# type-1_4_button.net
KiCad netlist of a schematic drawn in EAGLE
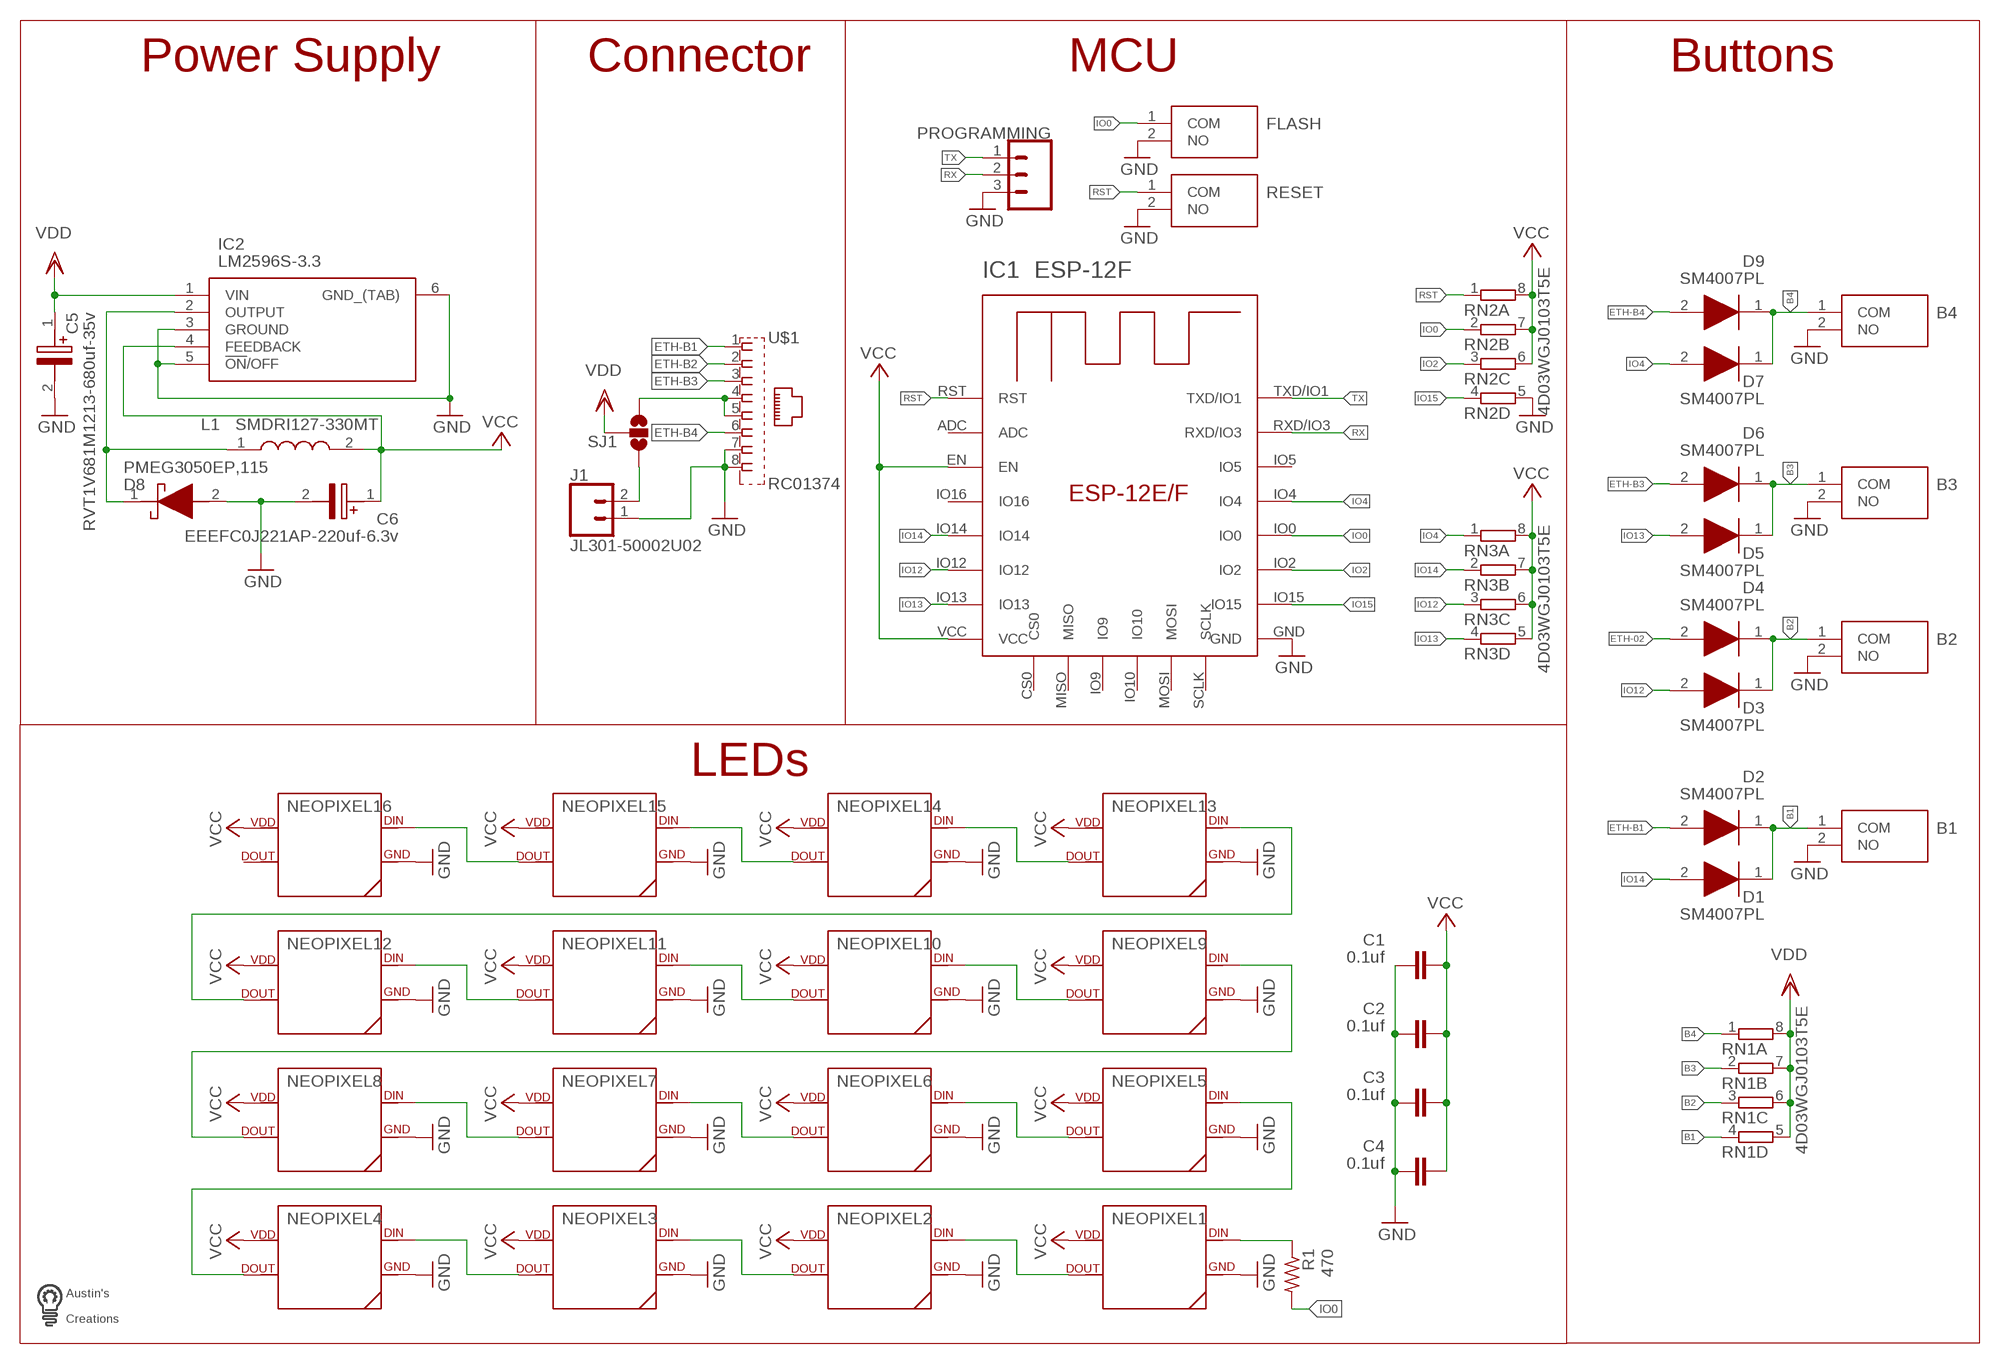
[diagram p0: schematic, sheet 1]

(export (version "E")
  (design (tool "Eeschema 10.0.6"))
  (components
    (comp (ref "B1")
      (value "PTS636_SM25F_SMTR_LFS")
      (footprint "eagle-import:PTS636SM25FSMTRLFS")
      (fields
        (field (name "ARROW_PART_NUMBER") "PTS636 SM25F SMTR LFS")
        (field (name "MOUSER_PART_NUMBER") "611-PTS636SM25FSMTRL")
      )
      (libsource (lib "eagle-import") (part "PTS636_SM25F_SMTR_LFS"))
    )
    (comp (ref "B2")
      (value "PTS636_SM25F_SMTR_LFS")
      (footprint "eagle-import:PTS636SM25FSMTRLFS")
      (fields
        (field (name "ARROW_PART_NUMBER") "PTS636 SM25F SMTR LFS")
        (field (name "MOUSER_PART_NUMBER") "611-PTS636SM25FSMTRL")
      )
      (libsource (lib "eagle-import") (part "PTS636_SM25F_SMTR_LFS"))
    )
    (comp (ref "B3")
      (value "PTS636_SM25F_SMTR_LFS")
      (footprint "eagle-import:PTS636SM25FSMTRLFS")
      (fields
        (field (name "ARROW_PART_NUMBER") "PTS636 SM25F SMTR LFS")
        (field (name "MOUSER_PART_NUMBER") "611-PTS636SM25FSMTRL")
      )
      (libsource (lib "eagle-import") (part "PTS636_SM25F_SMTR_LFS"))
    )
    (comp (ref "B4")
      (value "PTS636_SM25F_SMTR_LFS")
      (footprint "eagle-import:PTS636SM25FSMTRLFS")
      (fields
        (field (name "ARROW_PART_NUMBER") "PTS636 SM25F SMTR LFS")
        (field (name "MOUSER_PART_NUMBER") "611-PTS636SM25FSMTRL")
      )
      (libsource (lib "eagle-import") (part "PTS636_SM25F_SMTR_LFS"))
    )
    (comp (ref "C1")
      (value "0.1uf")
      (footprint "eagle-import:C0603")
      (libsource (lib "eagle-import") (part "C-EUC0603"))
    )
    (comp (ref "C2")
      (value "0.1uf")
      (footprint "eagle-import:C0603")
      (libsource (lib "eagle-import") (part "C-EUC0603"))
    )
    (comp (ref "C3")
      (value "0.1uf")
      (footprint "eagle-import:C0603")
      (libsource (lib "eagle-import") (part "C-EUC0603"))
    )
    (comp (ref "C4")
      (value "0.1uf")
      (footprint "eagle-import:C0603")
      (libsource (lib "eagle-import") (part "C-EUC0603"))
    )
    (comp (ref "C5")
      (value "RVT1V681M1213-680uf-35v")
      (footprint "eagle-import:CAPAE1350X1400N")
      (fields
        (field (name "MANUFACTURER_PART_NUMBER") "EEE-HD1V681AQ")
        (field (name "MOUSER_PART_NUMBER") "667-EEE-HD1V681AQ")
      )
      (libsource (lib "eagle-import") (part "EEE-HD1V681AQ"))
    )
    (comp (ref "C6")
      (value "EEEFC0J221AP-220uf-6.3v")
      (footprint "eagle-import:CAPAE830X650N")
      (fields (field (name "MANUFACTURER_PART_NUMBER") "EEEFC0J221AP"))
      (libsource (lib "eagle-import") (part "EEEFC0J221AP"))
    )
    (comp (ref "D1")
      (value "SM4007PL")
      (footprint "eagle-import:SODFL3718X125N")
      (libsource (lib "eagle-import") (part "SM4007PL"))
    )
    (comp (ref "D2")
      (value "SM4007PL")
      (footprint "eagle-import:SODFL3718X125N")
      (libsource (lib "eagle-import") (part "SM4007PL"))
    )
    (comp (ref "D3")
      (value "SM4007PL")
      (footprint "eagle-import:SODFL3718X125N")
      (libsource (lib "eagle-import") (part "SM4007PL"))
    )
    (comp (ref "D4")
      (value "SM4007PL")
      (footprint "eagle-import:SODFL3718X125N")
      (libsource (lib "eagle-import") (part "SM4007PL"))
    )
    (comp (ref "D5")
      (value "SM4007PL")
      (footprint "eagle-import:SODFL3718X125N")
      (libsource (lib "eagle-import") (part "SM4007PL"))
    )
    (comp (ref "D6")
      (value "SM4007PL")
      (footprint "eagle-import:SODFL3718X125N")
      (libsource (lib "eagle-import") (part "SM4007PL"))
    )
    (comp (ref "D7")
      (value "SM4007PL")
      (footprint "eagle-import:SODFL3718X125N")
      (libsource (lib "eagle-import") (part "SM4007PL"))
    )
    (comp (ref "D8")
      (value "PMEG3050EP,115")
      (footprint "eagle-import:PMEG3050EP115")
      (fields (field (name "MOUSER_PART_NUMBER") "771-PMEG3050EP115"))
      (libsource (lib "eagle-import") (part "PMEG3050EP,115"))
    )
    (comp (ref "D9")
      (value "SM4007PL")
      (footprint "eagle-import:SODFL3718X125N")
      (libsource (lib "eagle-import") (part "SM4007PL"))
    )
    (comp (ref "FLASH")
      (value "PTS636_SM25F_SMTR_LFS")
      (footprint "eagle-import:PTS636SM25FSMTRLFS")
      (fields
        (field (name "ARROW_PART_NUMBER") "PTS636 SM25F SMTR LFS")
        (field (name "MOUSER_PART_NUMBER") "611-PTS636SM25FSMTRL")
      )
      (libsource (lib "eagle-import") (part "PTS636_SM25F_SMTR_LFS"))
    )
    (comp (ref "IC1")
      (value "ESP-12F")
      (footprint "eagle-import:ESP-12E")
      (libsource (lib "eagle-import") (part "ESP-12E/F"))
    )
    (comp (ref "IC2")
      (value "LM2596S-3.3")
      (footprint "eagle-import:TO170P1435X465-6N")
      (fields
        (field (name "MANUFACTURER_PART_NUMBER") "LM2596S-3.3/NOPB")
        (field (name "MOUSER_PART_NUMBER") "926-LM2596S-3.3/NOPB")
      )
      (libsource (lib "eagle-import") (part "LM2596S-3.3_NOPB"))
    )
    (comp (ref "J1")
      (value "JL301-50002U02")
      (footprint "eagle-import:SCREWTERMINAL-5MM-2")
      (libsource (lib "eagle-import") (part "CONN_025MM"))
    )
    (comp (ref "L1")
      (value "SMDRI127-330MT")
      (footprint "eagle-import:INDPM120120X800N")
      (fields
        (field (name "MANUFACTURER_PART_NUMBER") "CDRH127/LDNP-330MC")
        (field (name "MOUSER_PART_NUMBER") "851-CDRH127LDNP330MC")
      )
      (libsource (lib "eagle-import") (part "CDRH127_LDNP-330MC"))
    )
    (comp (ref "NEOPIXEL1")
      (value "SK6812NEOPIXEL5050")
      (footprint "eagle-import:SK6812")
      (libsource (lib "eagle-import") (part "SK68125050NEOPIXEL"))
    )
    (comp (ref "NEOPIXEL2")
      (value "SK6812NEOPIXEL5050")
      (footprint "eagle-import:SK6812")
      (libsource (lib "eagle-import") (part "SK68125050NEOPIXEL"))
    )
    (comp (ref "NEOPIXEL3")
      (value "SK6812NEOPIXEL5050")
      (footprint "eagle-import:SK6812")
      (libsource (lib "eagle-import") (part "SK68125050NEOPIXEL"))
    )
    (comp (ref "NEOPIXEL4")
      (value "SK6812NEOPIXEL5050")
      (footprint "eagle-import:SK6812")
      (libsource (lib "eagle-import") (part "SK68125050NEOPIXEL"))
    )
    (comp (ref "NEOPIXEL5")
      (value "SK6812NEOPIXEL5050")
      (footprint "eagle-import:SK6812")
      (libsource (lib "eagle-import") (part "SK68125050NEOPIXEL"))
    )
    (comp (ref "NEOPIXEL6")
      (value "SK6812NEOPIXEL5050")
      (footprint "eagle-import:SK6812")
      (libsource (lib "eagle-import") (part "SK68125050NEOPIXEL"))
    )
    (comp (ref "NEOPIXEL7")
      (value "SK6812NEOPIXEL5050")
      (footprint "eagle-import:SK6812")
      (libsource (lib "eagle-import") (part "SK68125050NEOPIXEL"))
    )
    (comp (ref "NEOPIXEL8")
      (value "SK6812NEOPIXEL5050")
      (footprint "eagle-import:SK6812")
      (libsource (lib "eagle-import") (part "SK68125050NEOPIXEL"))
    )
    (comp (ref "NEOPIXEL9")
      (value "SK6812NEOPIXEL5050")
      (footprint "eagle-import:SK6812")
      (libsource (lib "eagle-import") (part "SK68125050NEOPIXEL"))
    )
    (comp (ref "NEOPIXEL10")
      (value "SK6812NEOPIXEL5050")
      (footprint "eagle-import:SK6812")
      (libsource (lib "eagle-import") (part "SK68125050NEOPIXEL"))
    )
    (comp (ref "NEOPIXEL11")
      (value "SK6812NEOPIXEL5050")
      (footprint "eagle-import:SK6812")
      (libsource (lib "eagle-import") (part "SK68125050NEOPIXEL"))
    )
    (comp (ref "NEOPIXEL12")
      (value "SK6812NEOPIXEL5050")
      (footprint "eagle-import:SK6812")
      (libsource (lib "eagle-import") (part "SK68125050NEOPIXEL"))
    )
    (comp (ref "NEOPIXEL13")
      (value "SK6812NEOPIXEL5050")
      (footprint "eagle-import:SK6812")
      (libsource (lib "eagle-import") (part "SK68125050NEOPIXEL"))
    )
    (comp (ref "NEOPIXEL14")
      (value "SK6812NEOPIXEL5050")
      (footprint "eagle-import:SK6812")
      (libsource (lib "eagle-import") (part "SK68125050NEOPIXEL"))
    )
    (comp (ref "NEOPIXEL15")
      (value "SK6812NEOPIXEL5050")
      (footprint "eagle-import:SK6812")
      (libsource (lib "eagle-import") (part "SK68125050NEOPIXEL"))
    )
    (comp (ref "NEOPIXEL16")
      (value "SK6812NEOPIXEL5050")
      (footprint "eagle-import:SK6812")
      (libsource (lib "eagle-import") (part "SK68125050NEOPIXEL"))
    )
    (comp (ref "PROGRAMMING")
      (value "455-1750-1-ND")
      (footprint "eagle-import:1X03")
      (libsource (lib "eagle-import") (part "CONN_03"))
    )
    (comp (ref "R1")
      (value "470")
      (footprint "eagle-import:R0603")
      (libsource (lib "eagle-import") (part "R-US_R0603"))
    )
    (comp (ref "RESET")
      (value "PTS636_SM25F_SMTR_LFS")
      (footprint "eagle-import:PTS636SM25FSMTRLFS")
      (fields
        (field (name "ARROW_PART_NUMBER") "PTS636 SM25F SMTR LFS")
        (field (name "MOUSER_PART_NUMBER") "611-PTS636SM25FSMTRL")
      )
      (libsource (lib "eagle-import") (part "PTS636_SM25F_SMTR_LFS"))
    )
    (comp (ref "RN1")
      (value "4R-N0603-ARC")
      (footprint "eagle-import:0603-ARC")
      (libsource (lib "eagle-import") (part "4R-N0603-ARC"))
    )
    (comp (ref "RN2")
      (value "4R-N0603-ARC")
      (footprint "eagle-import:0603-ARC")
      (libsource (lib "eagle-import") (part "4R-N0603-ARC"))
    )
    (comp (ref "RN3")
      (value "4R-N0603-ARC")
      (footprint "eagle-import:0603-ARC")
      (libsource (lib "eagle-import") (part "4R-N0603-ARC"))
    )
    (comp (ref "SJ1")
      (value "SOLDERJUMPER_2WAYPASTE1&2")
      (footprint "eagle-import:SJ_3_PASTE1&2")
      (libsource (lib "eagle-import") (part "SOLDERJUMPER_2WAYPASTE1&2"))
    )
    (comp (ref "U$1")
      (value "RC01374")
      (footprint "eagle-import:RC01374")
      (libsource (lib "eagle-import") (part "RC01374"))
    )
    (comp (ref "U$2")
      (value "LOGO")
      (footprint "eagle-import:LOGO")
      (libsource (lib "eagle-import") (part "LOGO"))
    )
  )
  (nets
    (net (code "1") (name "B1") (class "Default")
      (node (ref "B1") (pin "1") (pinfunction "COM_1") (pintype "bidirectional"))
      (node (ref "D1") (pin "1") (pinfunction "K_1") (pintype "bidirectional"))
      (node (ref "D2") (pin "1") (pinfunction "K_1") (pintype "bidirectional"))
      (node (ref "RN1") (pin "4") (pinfunction "1_4") (pintype "passive"))
    )
    (net (code "2") (name "B2") (class "Default")
      (node (ref "B2") (pin "1") (pinfunction "COM_1") (pintype "bidirectional"))
      (node (ref "D3") (pin "1") (pinfunction "K_1") (pintype "bidirectional"))
      (node (ref "D4") (pin "1") (pinfunction "K_1") (pintype "bidirectional"))
      (node (ref "RN1") (pin "3") (pinfunction "1_3") (pintype "passive"))
    )
    (net (code "3") (name "B3") (class "Default")
      (node (ref "B3") (pin "1") (pinfunction "COM_1") (pintype "bidirectional"))
      (node (ref "D5") (pin "1") (pinfunction "K_1") (pintype "bidirectional"))
      (node (ref "D6") (pin "1") (pinfunction "K_1") (pintype "bidirectional"))
      (node (ref "RN1") (pin "2") (pinfunction "1_2") (pintype "passive"))
    )
    (net (code "4") (name "B4") (class "Default")
      (node (ref "B4") (pin "1") (pinfunction "COM_1") (pintype "bidirectional"))
      (node (ref "D7") (pin "1") (pinfunction "K_1") (pintype "bidirectional"))
      (node (ref "D9") (pin "1") (pinfunction "K_1") (pintype "bidirectional"))
      (node (ref "RN1") (pin "1") (pinfunction "1_1") (pintype "passive"))
    )
    (net (code "5") (name "ETH-02") (class "Default")
      (node (ref "D4") (pin "2") (pinfunction "A_2") (pintype "bidirectional"))
    )
    (net (code "6") (name "ETH-B1") (class "Default")
      (node (ref "D2") (pin "2") (pinfunction "A_2") (pintype "bidirectional"))
      (node (ref "U$1") (pin "1") (pinfunction "1_1") (pintype "passive"))
    )
    (net (code "7") (name "ETH-B2") (class "Default")
      (node (ref "U$1") (pin "2") (pinfunction "2_2") (pintype "passive"))
    )
    (net (code "8") (name "ETH-B3") (class "Default")
      (node (ref "D6") (pin "2") (pinfunction "A_2") (pintype "bidirectional"))
      (node (ref "U$1") (pin "3") (pinfunction "3_3") (pintype "passive"))
    )
    (net (code "9") (name "ETH-B4") (class "Default")
      (node (ref "D9") (pin "2") (pinfunction "A_2") (pintype "bidirectional"))
      (node (ref "U$1") (pin "6") (pinfunction "6_6") (pintype "passive"))
    )
    (net (code "10") (name "GND") (class "Default")
      (node (ref "B1") (pin "2") (pinfunction "NO_2") (pintype "bidirectional"))
      (node (ref "B2") (pin "2") (pinfunction "NO_2") (pintype "bidirectional"))
      (node (ref "B3") (pin "2") (pinfunction "NO_2") (pintype "bidirectional"))
      (node (ref "B4") (pin "2") (pinfunction "NO_2") (pintype "bidirectional"))
      (node (ref "C1") (pin "1") (pinfunction "1_1") (pintype "passive"))
      (node (ref "C2") (pin "1") (pinfunction "1_1") (pintype "passive"))
      (node (ref "C3") (pin "1") (pinfunction "1_1") (pintype "passive"))
      (node (ref "C4") (pin "1") (pinfunction "1_1") (pintype "passive"))
      (node (ref "C5") (pin "2") (pinfunction "-_2") (pintype "bidirectional"))
      (node (ref "C6") (pin "2") (pinfunction "-_2") (pintype "bidirectional"))
      (node (ref "D8") (pin "2") (pinfunction "A_2") (pintype "bidirectional"))
      (node (ref "FLASH") (pin "2") (pinfunction "NO_2") (pintype "bidirectional"))
      (node (ref "IC1") (pin "GND") (pinfunction "GND_GND") (pintype "power_in"))
      (node (ref "IC2") (pin "3") (pinfunction "GROUND_3") (pintype "bidirectional"))
      (node (ref "IC2") (pin "5") (pinfunction "~{ON}/OFF_5") (pintype "bidirectional"))
      (node (ref "IC2") (pin "6") (pinfunction "GND_(TAB)_6") (pintype "power_in"))
      (node (ref "J1") (pin "1") (pinfunction "1_1") (pintype "passive"))
      (node (ref "NEOPIXEL1") (pin "3") (pinfunction "GND_3") (pintype "bidirectional"))
      (node (ref "NEOPIXEL10") (pin "3") (pinfunction "GND_3") (pintype "bidirectional"))
      (node (ref "NEOPIXEL11") (pin "3") (pinfunction "GND_3") (pintype "bidirectional"))
      (node (ref "NEOPIXEL12") (pin "3") (pinfunction "GND_3") (pintype "bidirectional"))
      (node (ref "NEOPIXEL13") (pin "3") (pinfunction "GND_3") (pintype "bidirectional"))
      (node (ref "NEOPIXEL14") (pin "3") (pinfunction "GND_3") (pintype "bidirectional"))
      (node (ref "NEOPIXEL15") (pin "3") (pinfunction "GND_3") (pintype "bidirectional"))
      (node (ref "NEOPIXEL16") (pin "3") (pinfunction "GND_3") (pintype "bidirectional"))
      (node (ref "NEOPIXEL2") (pin "3") (pinfunction "GND_3") (pintype "bidirectional"))
      (node (ref "NEOPIXEL3") (pin "3") (pinfunction "GND_3") (pintype "bidirectional"))
      (node (ref "NEOPIXEL4") (pin "3") (pinfunction "GND_3") (pintype "bidirectional"))
      (node (ref "NEOPIXEL5") (pin "3") (pinfunction "GND_3") (pintype "bidirectional"))
      (node (ref "NEOPIXEL6") (pin "3") (pinfunction "GND_3") (pintype "bidirectional"))
      (node (ref "NEOPIXEL7") (pin "3") (pinfunction "GND_3") (pintype "bidirectional"))
      (node (ref "NEOPIXEL8") (pin "3") (pinfunction "GND_3") (pintype "bidirectional"))
      (node (ref "NEOPIXEL9") (pin "3") (pinfunction "GND_3") (pintype "bidirectional"))
      (node (ref "PROGRAMMING") (pin "3") (pinfunction "3_3") (pintype "passive"))
      (node (ref "RESET") (pin "2") (pinfunction "NO_2") (pintype "bidirectional"))
      (node (ref "RN2") (pin "5") (pinfunction "2_5") (pintype "passive"))
      (node (ref "U$1") (pin "7") (pinfunction "7_7") (pintype "passive"))
      (node (ref "U$1") (pin "8") (pinfunction "8_8") (pintype "passive"))
    )
    (net (code "11") (name "IO0") (class "Default")
      (node (ref "FLASH") (pin "1") (pinfunction "COM_1") (pintype "bidirectional"))
      (node (ref "IC1") (pin "IO0") (pinfunction "IO0_IO0") (pintype "bidirectional"))
      (node (ref "R1") (pin "2") (pinfunction "2_2") (pintype "passive"))
      (node (ref "RN2") (pin "2") (pinfunction "1_2") (pintype "passive"))
    )
    (net (code "12") (name "IO2") (class "Default")
      (node (ref "IC1") (pin "IO2") (pinfunction "IO2_IO2") (pintype "bidirectional"))
      (node (ref "RN2") (pin "3") (pinfunction "1_3") (pintype "passive"))
    )
    (net (code "13") (name "IO4") (class "Default")
      (node (ref "D7") (pin "2") (pinfunction "A_2") (pintype "bidirectional"))
      (node (ref "IC1") (pin "IO4") (pinfunction "IO4_IO4") (pintype "bidirectional"))
      (node (ref "RN3") (pin "1") (pinfunction "1_1") (pintype "passive"))
    )
    (net (code "14") (name "IO12") (class "Default")
      (node (ref "D3") (pin "2") (pinfunction "A_2") (pintype "bidirectional"))
      (node (ref "IC1") (pin "IO12") (pinfunction "IO12_IO12") (pintype "bidirectional"))
      (node (ref "RN3") (pin "3") (pinfunction "1_3") (pintype "passive"))
    )
    (net (code "15") (name "IO13") (class "Default")
      (node (ref "D5") (pin "2") (pinfunction "A_2") (pintype "bidirectional"))
      (node (ref "IC1") (pin "IO13") (pinfunction "IO13_IO13") (pintype "bidirectional"))
      (node (ref "RN3") (pin "4") (pinfunction "1_4") (pintype "passive"))
    )
    (net (code "16") (name "IO14") (class "Default")
      (node (ref "D1") (pin "2") (pinfunction "A_2") (pintype "bidirectional"))
      (node (ref "IC1") (pin "IO14") (pinfunction "IO14_IO14") (pintype "bidirectional"))
      (node (ref "RN3") (pin "2") (pinfunction "1_2") (pintype "passive"))
    )
    (net (code "17") (name "IO15") (class "Default")
      (node (ref "IC1") (pin "IO15") (pinfunction "IO15_IO15") (pintype "bidirectional"))
      (node (ref "RN2") (pin "4") (pinfunction "1_4") (pintype "passive"))
    )
    (net (code "18") (name "Net-(D8-K)") (class "Default")
      (node (ref "D8") (pin "1") (pinfunction "K_1") (pintype "bidirectional"))
      (node (ref "IC2") (pin "2") (pinfunction "OUTPUT_2") (pintype "output"))
      (node (ref "L1") (pin "1") (pinfunction "1_1") (pintype "bidirectional"))
    )
    (net (code "19") (name "Net-(J1-Pad2)") (class "Default")
      (node (ref "J1") (pin "2") (pinfunction "2_2") (pintype "passive"))
      (node (ref "SJ1") (pin "3") (pinfunction "3_3") (pintype "passive"))
    )
    (net (code "20") (name "Net-(NEOPIXEL1-DIN)") (class "Default")
      (node (ref "NEOPIXEL1") (pin "4") (pinfunction "DIN_4") (pintype "bidirectional"))
      (node (ref "R1") (pin "1") (pinfunction "1_1") (pintype "passive"))
    )
    (net (code "21") (name "Net-(NEOPIXEL1-DOUT)") (class "Default")
      (node (ref "NEOPIXEL1") (pin "2") (pinfunction "DOUT_2") (pintype "bidirectional"))
      (node (ref "NEOPIXEL2") (pin "4") (pinfunction "DIN_4") (pintype "bidirectional"))
    )
    (net (code "22") (name "Net-(NEOPIXEL2-DOUT)") (class "Default")
      (node (ref "NEOPIXEL2") (pin "2") (pinfunction "DOUT_2") (pintype "bidirectional"))
      (node (ref "NEOPIXEL3") (pin "4") (pinfunction "DIN_4") (pintype "bidirectional"))
    )
    (net (code "23") (name "Net-(NEOPIXEL3-DOUT)") (class "Default")
      (node (ref "NEOPIXEL3") (pin "2") (pinfunction "DOUT_2") (pintype "bidirectional"))
      (node (ref "NEOPIXEL4") (pin "4") (pinfunction "DIN_4") (pintype "bidirectional"))
    )
    (net (code "24") (name "Net-(NEOPIXEL4-DOUT)") (class "Default")
      (node (ref "NEOPIXEL4") (pin "2") (pinfunction "DOUT_2") (pintype "bidirectional"))
      (node (ref "NEOPIXEL5") (pin "4") (pinfunction "DIN_4") (pintype "bidirectional"))
    )
    (net (code "25") (name "Net-(NEOPIXEL5-DOUT)") (class "Default")
      (node (ref "NEOPIXEL5") (pin "2") (pinfunction "DOUT_2") (pintype "bidirectional"))
      (node (ref "NEOPIXEL6") (pin "4") (pinfunction "DIN_4") (pintype "bidirectional"))
    )
    (net (code "26") (name "Net-(NEOPIXEL6-DOUT)") (class "Default")
      (node (ref "NEOPIXEL6") (pin "2") (pinfunction "DOUT_2") (pintype "bidirectional"))
      (node (ref "NEOPIXEL7") (pin "4") (pinfunction "DIN_4") (pintype "bidirectional"))
    )
    (net (code "27") (name "Net-(NEOPIXEL7-DOUT)") (class "Default")
      (node (ref "NEOPIXEL7") (pin "2") (pinfunction "DOUT_2") (pintype "bidirectional"))
      (node (ref "NEOPIXEL8") (pin "4") (pinfunction "DIN_4") (pintype "bidirectional"))
    )
    (net (code "28") (name "Net-(NEOPIXEL8-DOUT)") (class "Default")
      (node (ref "NEOPIXEL8") (pin "2") (pinfunction "DOUT_2") (pintype "bidirectional"))
      (node (ref "NEOPIXEL9") (pin "4") (pinfunction "DIN_4") (pintype "bidirectional"))
    )
    (net (code "29") (name "Net-(NEOPIXEL10-DIN)") (class "Default")
      (node (ref "NEOPIXEL10") (pin "4") (pinfunction "DIN_4") (pintype "bidirectional"))
      (node (ref "NEOPIXEL9") (pin "2") (pinfunction "DOUT_2") (pintype "bidirectional"))
    )
    (net (code "30") (name "Net-(NEOPIXEL10-DOUT)") (class "Default")
      (node (ref "NEOPIXEL10") (pin "2") (pinfunction "DOUT_2") (pintype "bidirectional"))
      (node (ref "NEOPIXEL11") (pin "4") (pinfunction "DIN_4") (pintype "bidirectional"))
    )
    (net (code "31") (name "Net-(NEOPIXEL11-DOUT)") (class "Default")
      (node (ref "NEOPIXEL11") (pin "2") (pinfunction "DOUT_2") (pintype "bidirectional"))
      (node (ref "NEOPIXEL12") (pin "4") (pinfunction "DIN_4") (pintype "bidirectional"))
    )
    (net (code "32") (name "Net-(NEOPIXEL12-DOUT)") (class "Default")
      (node (ref "NEOPIXEL12") (pin "2") (pinfunction "DOUT_2") (pintype "bidirectional"))
      (node (ref "NEOPIXEL13") (pin "4") (pinfunction "DIN_4") (pintype "bidirectional"))
    )
    (net (code "33") (name "Net-(NEOPIXEL13-DOUT)") (class "Default")
      (node (ref "NEOPIXEL13") (pin "2") (pinfunction "DOUT_2") (pintype "bidirectional"))
      (node (ref "NEOPIXEL14") (pin "4") (pinfunction "DIN_4") (pintype "bidirectional"))
    )
    (net (code "34") (name "Net-(NEOPIXEL14-DOUT)") (class "Default")
      (node (ref "NEOPIXEL14") (pin "2") (pinfunction "DOUT_2") (pintype "bidirectional"))
      (node (ref "NEOPIXEL15") (pin "4") (pinfunction "DIN_4") (pintype "bidirectional"))
    )
    (net (code "35") (name "Net-(NEOPIXEL15-DOUT)") (class "Default")
      (node (ref "NEOPIXEL15") (pin "2") (pinfunction "DOUT_2") (pintype "bidirectional"))
      (node (ref "NEOPIXEL16") (pin "4") (pinfunction "DIN_4") (pintype "bidirectional"))
    )
    (net (code "36") (name "Net-(SJ1-Pad1)") (class "Default")
      (node (ref "SJ1") (pin "1") (pinfunction "1_1") (pintype "passive"))
      (node (ref "U$1") (pin "4") (pinfunction "4_4") (pintype "passive"))
      (node (ref "U$1") (pin "5") (pinfunction "5_5") (pintype "passive"))
    )
    (net (code "37") (name "RST") (class "Default")
      (node (ref "IC1") (pin "RST") (pinfunction "RST_RST") (pintype "input"))
      (node (ref "RESET") (pin "1") (pinfunction "COM_1") (pintype "bidirectional"))
      (node (ref "RN2") (pin "1") (pinfunction "1_1") (pintype "passive"))
    )
    (net (code "38") (name "RX") (class "Default")
      (node (ref "IC1") (pin "RXD/IO3") (pinfunction "RXD/IO3_RXD/IO3") (pintype "bidirectional"))
      (node (ref "PROGRAMMING") (pin "2") (pinfunction "2_2") (pintype "passive"))
    )
    (net (code "39") (name "TX") (class "Default")
      (node (ref "IC1") (pin "TXD/IO1") (pinfunction "TXD/IO1_TXD/IO1") (pintype "bidirectional"))
      (node (ref "PROGRAMMING") (pin "1") (pinfunction "1_1") (pintype "passive"))
    )
    (net (code "40") (name "VCC") (class "Default")
      (node (ref "C1") (pin "2") (pinfunction "2_2") (pintype "passive"))
      (node (ref "C2") (pin "2") (pinfunction "2_2") (pintype "passive"))
      (node (ref "C3") (pin "2") (pinfunction "2_2") (pintype "passive"))
      (node (ref "C4") (pin "2") (pinfunction "2_2") (pintype "passive"))
      (node (ref "C6") (pin "1") (pinfunction "+_1") (pintype "bidirectional"))
      (node (ref "IC1") (pin "EN") (pinfunction "EN_EN") (pintype "bidirectional"))
      (node (ref "IC1") (pin "VCC") (pinfunction "VCC_VCC") (pintype "power_in"))
      (node (ref "IC2") (pin "4") (pinfunction "FEEDBACK_4") (pintype "bidirectional"))
      (node (ref "L1") (pin "2") (pinfunction "2_2") (pintype "bidirectional"))
      (node (ref "NEOPIXEL1") (pin "1") (pinfunction "VDD_1") (pintype "bidirectional"))
      (node (ref "NEOPIXEL10") (pin "1") (pinfunction "VDD_1") (pintype "bidirectional"))
      (node (ref "NEOPIXEL11") (pin "1") (pinfunction "VDD_1") (pintype "bidirectional"))
      (node (ref "NEOPIXEL12") (pin "1") (pinfunction "VDD_1") (pintype "bidirectional"))
      (node (ref "NEOPIXEL13") (pin "1") (pinfunction "VDD_1") (pintype "bidirectional"))
      (node (ref "NEOPIXEL14") (pin "1") (pinfunction "VDD_1") (pintype "bidirectional"))
      (node (ref "NEOPIXEL15") (pin "1") (pinfunction "VDD_1") (pintype "bidirectional"))
      (node (ref "NEOPIXEL16") (pin "1") (pinfunction "VDD_1") (pintype "bidirectional"))
      (node (ref "NEOPIXEL2") (pin "1") (pinfunction "VDD_1") (pintype "bidirectional"))
      (node (ref "NEOPIXEL3") (pin "1") (pinfunction "VDD_1") (pintype "bidirectional"))
      (node (ref "NEOPIXEL4") (pin "1") (pinfunction "VDD_1") (pintype "bidirectional"))
      (node (ref "NEOPIXEL5") (pin "1") (pinfunction "VDD_1") (pintype "bidirectional"))
      (node (ref "NEOPIXEL6") (pin "1") (pinfunction "VDD_1") (pintype "bidirectional"))
      (node (ref "NEOPIXEL7") (pin "1") (pinfunction "VDD_1") (pintype "bidirectional"))
      (node (ref "NEOPIXEL8") (pin "1") (pinfunction "VDD_1") (pintype "bidirectional"))
      (node (ref "NEOPIXEL9") (pin "1") (pinfunction "VDD_1") (pintype "bidirectional"))
      (node (ref "RN2") (pin "6") (pinfunction "2_6") (pintype "passive"))
      (node (ref "RN2") (pin "7") (pinfunction "2_7") (pintype "passive"))
      (node (ref "RN2") (pin "8") (pinfunction "2_8") (pintype "passive"))
      (node (ref "RN3") (pin "5") (pinfunction "2_5") (pintype "passive"))
      (node (ref "RN3") (pin "6") (pinfunction "2_6") (pintype "passive"))
      (node (ref "RN3") (pin "7") (pinfunction "2_7") (pintype "passive"))
      (node (ref "RN3") (pin "8") (pinfunction "2_8") (pintype "passive"))
    )
    (net (code "41") (name "VDD") (class "Default")
      (node (ref "C5") (pin "1") (pinfunction "+_1") (pintype "bidirectional"))
      (node (ref "IC2") (pin "1") (pinfunction "VIN_1") (pintype "input"))
      (node (ref "RN1") (pin "5") (pinfunction "2_5") (pintype "passive"))
      (node (ref "RN1") (pin "6") (pinfunction "2_6") (pintype "passive"))
      (node (ref "RN1") (pin "7") (pinfunction "2_7") (pintype "passive"))
      (node (ref "RN1") (pin "8") (pinfunction "2_8") (pintype "passive"))
      (node (ref "SJ1") (pin "2") (pinfunction "2_2") (pintype "passive"))
    )
    (net (code "42") (name "unconnected-(IC1-PadADC)") (class "Default")
      (node (ref "IC1") (pin "ADC") (pinfunction "ADC_ADC") (pintype "bidirectional"))
    )
    (net (code "43") (name "unconnected-(IC1-PadCS0)") (class "Default")
      (node (ref "IC1") (pin "CS0") (pinfunction "CS0_CS0") (pintype "bidirectional"))
    )
    (net (code "44") (name "unconnected-(IC1-PadIO5)") (class "Default")
      (node (ref "IC1") (pin "IO5") (pinfunction "IO5_IO5") (pintype "bidirectional"))
    )
    (net (code "45") (name "unconnected-(IC1-PadIO9)") (class "Default")
      (node (ref "IC1") (pin "IO9") (pinfunction "IO9_IO9") (pintype "bidirectional"))
    )
    (net (code "46") (name "unconnected-(IC1-PadIO10)") (class "Default")
      (node (ref "IC1") (pin "IO10") (pinfunction "IO10_IO10") (pintype "bidirectional"))
    )
    (net (code "47") (name "unconnected-(IC1-PadIO16)") (class "Default")
      (node (ref "IC1") (pin "IO16") (pinfunction "IO16_IO16") (pintype "bidirectional"))
    )
    (net (code "48") (name "unconnected-(IC1-PadMISO)") (class "Default")
      (node (ref "IC1") (pin "MISO") (pinfunction "MISO_MISO") (pintype "bidirectional"))
    )
    (net (code "49") (name "unconnected-(IC1-PadMOSI)") (class "Default")
      (node (ref "IC1") (pin "MOSI") (pinfunction "MOSI_MOSI") (pintype "bidirectional"))
    )
    (net (code "50") (name "unconnected-(IC1-PadSCLK)") (class "Default")
      (node (ref "IC1") (pin "SCLK") (pinfunction "SCLK_SCLK") (pintype "bidirectional"))
    )
    (net (code "51") (name "unconnected-(NEOPIXEL16-DOUT-Pad2)") (class "Default")
      (node (ref "NEOPIXEL16") (pin "2") (pinfunction "DOUT_2") (pintype "bidirectional"))
    )
  )
)
